# PSocC_Motor_Driver_Design_3.net
KiCad netlist of a schematic drawn in EAGLE
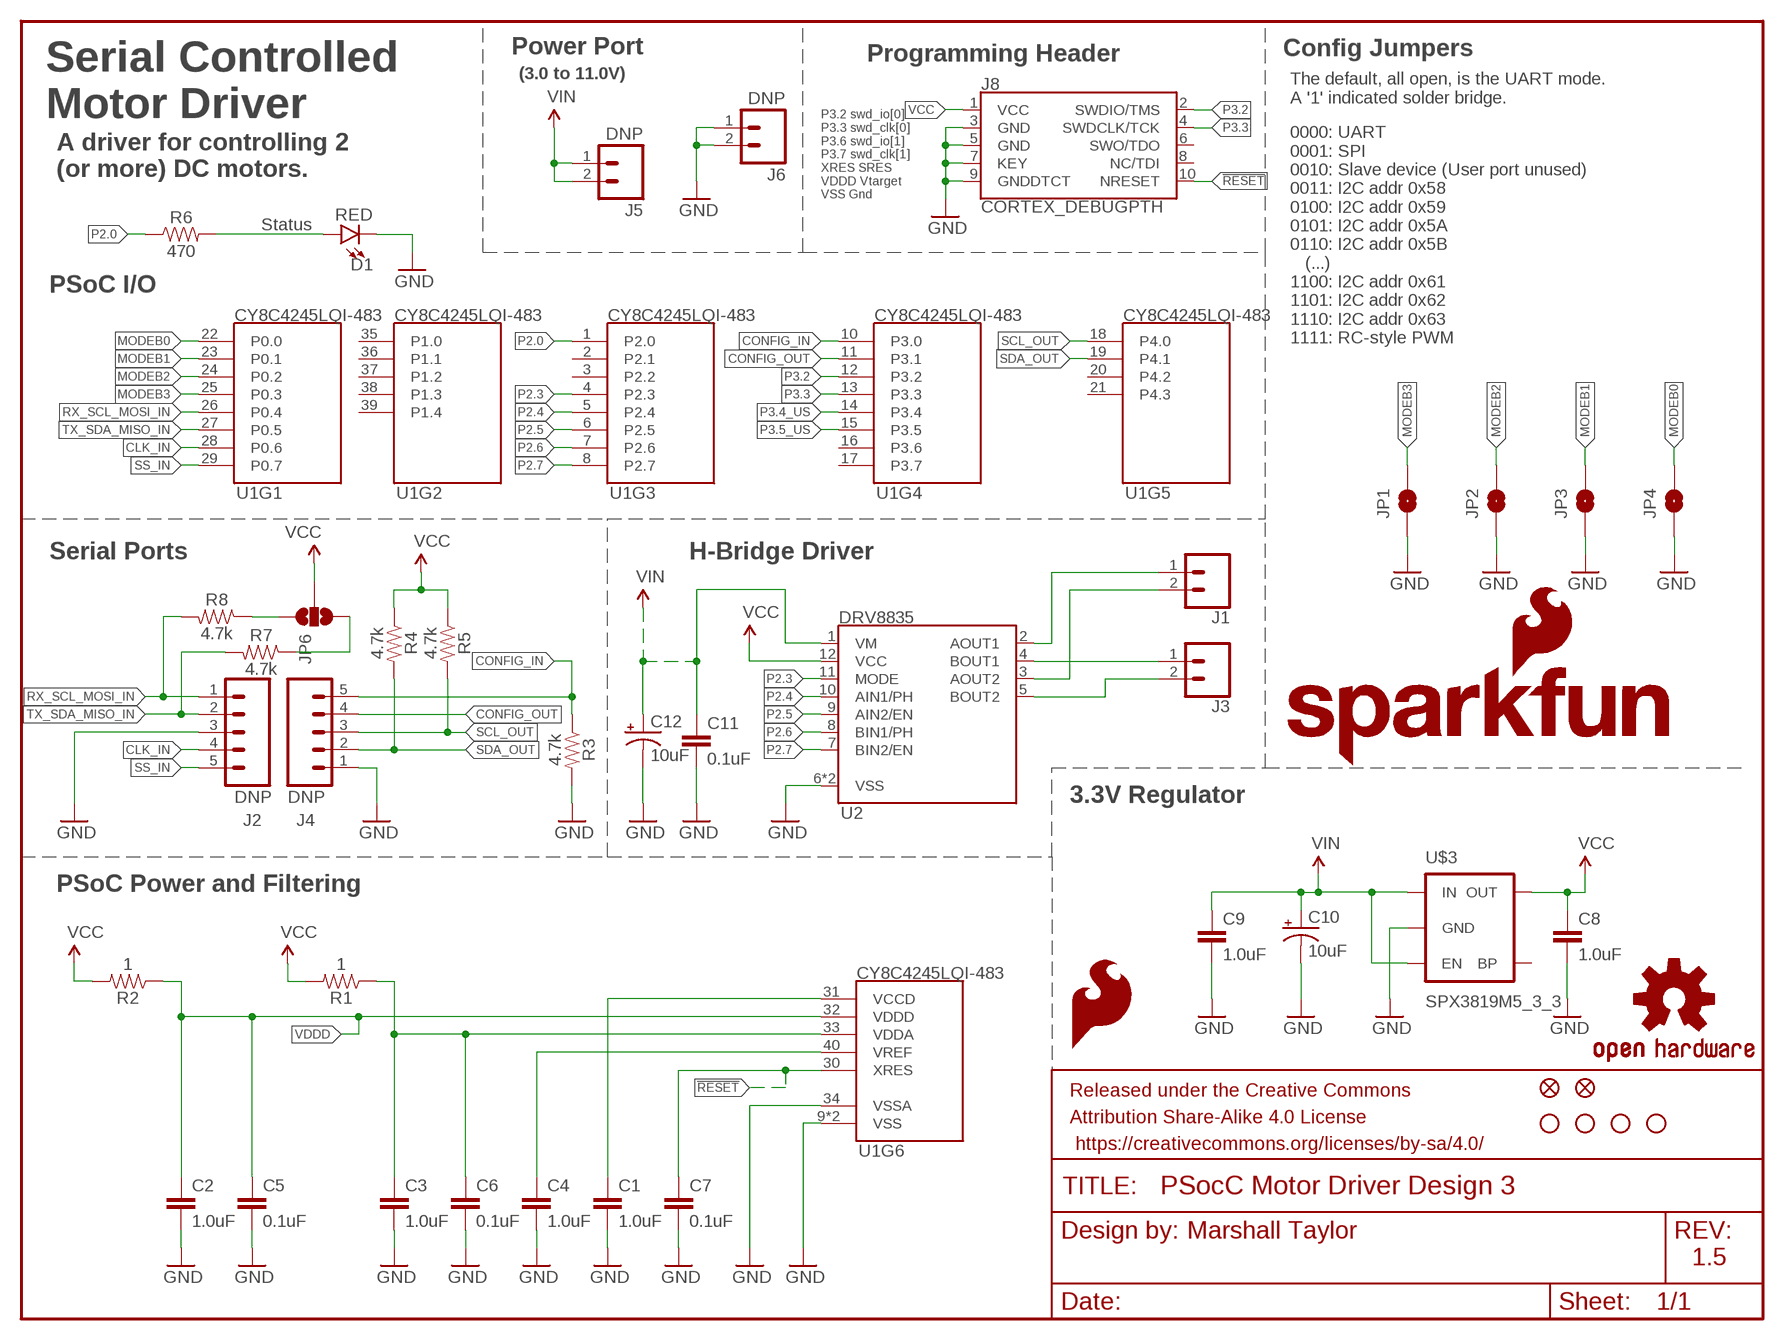
[diagram p0: schematic, sheet 1]

(export (version "E")
  (design (tool "Eeschema 10.0.6"))
  (components
    (comp (ref "C1")
      (value "1.0uF")
      (footprint "eagle-import:0402")
      (libsource (lib "eagle-import") (part "1.0UF-0402-16V-10%"))
    )
    (comp (ref "C2")
      (value "1.0uF")
      (footprint "eagle-import:0402")
      (libsource (lib "eagle-import") (part "1.0UF-0402-16V-10%"))
    )
    (comp (ref "C3")
      (value "1.0uF")
      (footprint "eagle-import:0402")
      (libsource (lib "eagle-import") (part "1.0UF-0402-16V-10%"))
    )
    (comp (ref "C4")
      (value "1.0uF")
      (footprint "eagle-import:0402")
      (libsource (lib "eagle-import") (part "1.0UF-0402-16V-10%"))
    )
    (comp (ref "C5")
      (value "0.1uF")
      (footprint "eagle-import:0402")
      (libsource (lib "eagle-import") (part "0.1UF-0402-16V-10%"))
    )
    (comp (ref "C6")
      (value "0.1uF")
      (footprint "eagle-import:0402")
      (libsource (lib "eagle-import") (part "0.1UF-0402-16V-10%"))
    )
    (comp (ref "C7")
      (value "0.1uF")
      (footprint "eagle-import:0402")
      (libsource (lib "eagle-import") (part "0.1UF-0402-16V-10%"))
    )
    (comp (ref "C8")
      (value "1.0uF")
      (footprint "eagle-import:0402")
      (libsource (lib "eagle-import") (part "1.0UF-0402-16V-10%"))
    )
    (comp (ref "C9")
      (value "1.0uF")
      (footprint "eagle-import:0402")
      (libsource (lib "eagle-import") (part "1.0UF-0402-16V-10%"))
    )
    (comp (ref "C10")
      (value "10uF")
      (footprint "eagle-import:EIA3216")
      (libsource (lib "eagle-import") (part "10UF-POLAR-EIA3216-16V-10%(TANT)"))
    )
    (comp (ref "C11")
      (value "0.1uF")
      (footprint "eagle-import:0402")
      (libsource (lib "eagle-import") (part "0.1UF-0402-16V-10%"))
    )
    (comp (ref "C12")
      (value "10uF")
      (footprint "eagle-import:EIA3216")
      (libsource (lib "eagle-import") (part "10UF-POLAR-EIA3216-16V-10%(TANT)"))
    )
    (comp (ref "D1")
      (value "RED")
      (footprint "eagle-import:LED-0603")
      (libsource (lib "eagle-import") (part "LED-RED0603"))
    )
    (comp (ref "FD1")
      (value "FIDUCIALUFIDUCIAL")
      (footprint "eagle-import:MICRO-FIDUCIAL")
      (libsource (lib "eagle-import") (part "FIDUCIALUFIDUCIAL"))
    )
    (comp (ref "FD2")
      (value "FIDUCIALUFIDUCIAL")
      (footprint "eagle-import:MICRO-FIDUCIAL")
      (libsource (lib "eagle-import") (part "FIDUCIALUFIDUCIAL"))
    )
    (comp (ref "FRAME1")
      (value "FRAME-LETTER")
      (footprint "eagle-import:CREATIVE_COMMONS")
      (libsource (lib "eagle-import") (part "FRAME-LETTER"))
    )
    (comp (ref "H1")
      (value "STAND-OFF")
      (footprint "eagle-import:STAND-OFF")
      (libsource (lib "eagle-import") (part "STAND-OFF"))
    )
    (comp (ref "H2")
      (value "STAND-OFF")
      (footprint "eagle-import:STAND-OFF")
      (libsource (lib "eagle-import") (part "STAND-OFF"))
    )
    (comp (ref "H3")
      (value "STAND-OFF")
      (footprint "eagle-import:STAND-OFF")
      (libsource (lib "eagle-import") (part "STAND-OFF"))
    )
    (comp (ref "H4")
      (value "STAND-OFF")
      (footprint "eagle-import:STAND-OFF")
      (libsource (lib "eagle-import") (part "STAND-OFF"))
    )
    (comp (ref "J1")
      (value "CONN_021X02_NO_SILK")
      (footprint "eagle-import:1X02_NO_SILK")
      (libsource (lib "eagle-import") (part "CONN_021X02_NO_SILK"))
    )
    (comp (ref "J2")
      (value "DNP")
      (footprint "eagle-import:1X05")
      (libsource (lib "eagle-import") (part "M05PTH"))
    )
    (comp (ref "J3")
      (value "CONN_021X02_NO_SILK")
      (footprint "eagle-import:1X02_NO_SILK")
      (libsource (lib "eagle-import") (part "CONN_021X02_NO_SILK"))
    )
    (comp (ref "J4")
      (value "DNP")
      (footprint "eagle-import:1X05")
      (libsource (lib "eagle-import") (part "M05PTH"))
    )
    (comp (ref "J5")
      (value "DNP")
      (footprint "eagle-import:1X02@1")
      (libsource (lib "eagle-import") (part "M02PTH"))
    )
    (comp (ref "J6")
      (value "DNP")
      (footprint "eagle-import:1X02@1")
      (libsource (lib "eagle-import") (part "M02PTH"))
    )
    (comp (ref "J8")
      (value "CORTEX_DEBUGPTH")
      (footprint "eagle-import:2X5-PTH-1.27MM")
      (libsource (lib "eagle-import") (part "CORTEX_DEBUGPTH"))
    )
    (comp (ref "JP1")
      (value "JUMPER-PAD-2")
      (footprint "eagle-import:PAD-JUMPER-2-NO_YES_SILK")
      (libsource (lib "eagle-import") (part "JUMPER-PAD-2-NOYES_SILK"))
    )
    (comp (ref "JP2")
      (value "JUMPER-PAD-2")
      (footprint "eagle-import:PAD-JUMPER-2-NO_YES_SILK")
      (libsource (lib "eagle-import") (part "JUMPER-PAD-2-NOYES_SILK"))
    )
    (comp (ref "JP3")
      (value "JUMPER-PAD-2")
      (footprint "eagle-import:PAD-JUMPER-2-NO_YES_SILK")
      (libsource (lib "eagle-import") (part "JUMPER-PAD-2-NOYES_SILK"))
    )
    (comp (ref "JP4")
      (value "JUMPER-PAD-2")
      (footprint "eagle-import:PAD-JUMPER-2-NO_YES_SILK")
      (libsource (lib "eagle-import") (part "JUMPER-PAD-2-NOYES_SILK"))
    )
    (comp (ref "JP6")
      (value "JUMPER-PAD-3-NOYES_SILK")
      (footprint "eagle-import:PAD-JUMPER-3-NO_YES_SILK")
      (libsource (lib "eagle-import") (part "JUMPER-PAD-3-NOYES_SILK"))
    )
    (comp (ref "LOGO1")
      (value "SFE_LOGO_FLAME.1_INCH")
      (footprint "eagle-import:SFE_LOGO_FLAME_.1")
      (libsource (lib "eagle-import") (part "SFE_LOGO_FLAME.1_INCH"))
    )
    (comp (ref "LOGO2")
      (value "OSHW-LOGOMINI")
      (footprint "eagle-import:OSHW-LOGO-MINI")
      (libsource (lib "eagle-import") (part "OSHW-LOGOMINI"))
    )
    (comp (ref "LOGO3")
      (value "SFE_LOGO_NAME_FLAME.1_INCH")
      (footprint "eagle-import:SFE_LOGO_NAME_FLAME_.1")
      (libsource (lib "eagle-import") (part "SFE_LOGO_NAME_FLAME.1_INCH"))
    )
    (comp (ref "R1")
      (value "1")
      (footprint "eagle-import:0603")
      (libsource (lib "eagle-import") (part "1OHM-0603-1/10W-1%"))
    )
    (comp (ref "R2")
      (value "1")
      (footprint "eagle-import:0603")
      (libsource (lib "eagle-import") (part "1OHM-0603-1/10W-1%"))
    )
    (comp (ref "R3")
      (value "4.7k")
      (footprint "eagle-import:0603")
      (libsource (lib "eagle-import") (part "4.7KOHM-0603-1/10W-1%"))
    )
    (comp (ref "R4")
      (value "4.7k")
      (footprint "eagle-import:0603")
      (libsource (lib "eagle-import") (part "4.7KOHM-0603-1/10W-1%"))
    )
    (comp (ref "R5")
      (value "4.7k")
      (footprint "eagle-import:0603")
      (libsource (lib "eagle-import") (part "4.7KOHM-0603-1/10W-1%"))
    )
    (comp (ref "R6")
      (value "470")
      (footprint "eagle-import:0603")
      (libsource (lib "eagle-import") (part "470OHM-0603-1/10W-1%"))
    )
    (comp (ref "R7")
      (value "4.7k")
      (footprint "eagle-import:0603")
      (libsource (lib "eagle-import") (part "4.7KOHM-0603-1/10W-1%"))
    )
    (comp (ref "R8")
      (value "4.7k")
      (footprint "eagle-import:0603")
      (libsource (lib "eagle-import") (part "4.7KOHM-0603-1/10W-1%"))
    )
    (comp (ref "U$3")
      (value "SPX3819M5_3_3")
      (footprint "eagle-import:SOT-23-5-VREG")
      (libsource (lib "eagle-import") (part "SPX3819"))
    )
    (comp (ref "U1")
      (value "CY8C4245LQI-483")
      (footprint "eagle-import:QFN-40")
      (libsource (lib "eagle-import") (part "CY8C4245LQI"))
    )
    (comp (ref "U2")
      (value "DRV8835")
      (footprint "eagle-import:WSON-12")
      (fields (field (name "PROD_ID") "IC-13342"))
      (libsource (lib "eagle-import") (part "DRV883X"))
    )
  )
  (nets
    (net (code "1") (name "/~{RESET}") (class "Default")
      (node (ref "C7") (pin "1") (pinfunction "1_1") (pintype "passive"))
      (node (ref "J8") (pin "10") (pinfunction "NRESET_10") (pintype "bidirectional"))
      (node (ref "U1") (pin "30") (pinfunction "XRES_30") (pintype "bidirectional"))
    )
    (net (code "2") (name "CLK_IN") (class "Default")
      (node (ref "J2") (pin "4") (pinfunction "4_4") (pintype "passive"))
      (node (ref "U1") (pin "28") (pinfunction "P0.6_28") (pintype "bidirectional"))
    )
    (net (code "3") (name "CONFIG_IN") (class "Default")
      (node (ref "J4") (pin "5") (pinfunction "5_5") (pintype "passive"))
      (node (ref "R3") (pin "1") (pinfunction "1_1") (pintype "passive"))
      (node (ref "U1") (pin "10") (pinfunction "P3.0_10") (pintype "bidirectional"))
    )
    (net (code "4") (name "CONFIG_OUT") (class "Default")
      (node (ref "J4") (pin "4") (pinfunction "4_4") (pintype "passive"))
      (node (ref "U1") (pin "11") (pinfunction "P3.1_11") (pintype "bidirectional"))
    )
    (net (code "5") (name "GND") (class "Default")
      (node (ref "C1") (pin "2") (pinfunction "2_2") (pintype "passive"))
      (node (ref "C10") (pin "-") (pinfunction "-_-") (pintype "passive"))
      (node (ref "C11") (pin "2") (pinfunction "2_2") (pintype "passive"))
      (node (ref "C12") (pin "-") (pinfunction "-_-") (pintype "passive"))
      (node (ref "C2") (pin "2") (pinfunction "2_2") (pintype "passive"))
      (node (ref "C3") (pin "2") (pinfunction "2_2") (pintype "passive"))
      (node (ref "C4") (pin "2") (pinfunction "2_2") (pintype "passive"))
      (node (ref "C5") (pin "2") (pinfunction "2_2") (pintype "passive"))
      (node (ref "C6") (pin "2") (pinfunction "2_2") (pintype "passive"))
      (node (ref "C7") (pin "2") (pinfunction "2_2") (pintype "passive"))
      (node (ref "C8") (pin "2") (pinfunction "2_2") (pintype "passive"))
      (node (ref "C9") (pin "2") (pinfunction "2_2") (pintype "passive"))
      (node (ref "D1") (pin "C") (pinfunction "C_C") (pintype "passive"))
      (node (ref "J2") (pin "3") (pinfunction "3_3") (pintype "passive"))
      (node (ref "J4") (pin "1") (pinfunction "1_1") (pintype "passive"))
      (node (ref "J6") (pin "1") (pinfunction "1_1") (pintype "passive"))
      (node (ref "J6") (pin "2") (pinfunction "2_2") (pintype "passive"))
      (node (ref "J8") (pin "3") (pinfunction "GND_3") (pintype "bidirectional"))
      (node (ref "J8") (pin "5") (pinfunction "GND_5") (pintype "bidirectional"))
      (node (ref "J8") (pin "7") (pinfunction "KEY_7") (pintype "bidirectional"))
      (node (ref "J8") (pin "9") (pinfunction "GNDDTCT_9") (pintype "bidirectional"))
      (node (ref "JP1") (pin "1") (pinfunction "1_1") (pintype "passive"))
      (node (ref "JP2") (pin "1") (pinfunction "1_1") (pintype "passive"))
      (node (ref "JP3") (pin "1") (pinfunction "1_1") (pintype "passive"))
      (node (ref "JP4") (pin "1") (pinfunction "1_1") (pintype "passive"))
      (node (ref "R3") (pin "2") (pinfunction "2_2") (pintype "passive"))
      (node (ref "U$3") (pin "2") (pinfunction "GND_2") (pintype "input"))
      (node (ref "U1") (pin "34") (pinfunction "VSSA_34") (pintype "bidirectional"))
      (node (ref "U1") (pin "9") (pinfunction "VSS_9") (pintype "bidirectional"))
      (node (ref "U1") (pin "EP") (pinfunction "VSS_EP") (pintype "bidirectional"))
      (node (ref "U2") (pin "6") (pinfunction "VSS_6") (pintype "bidirectional"))
      (node (ref "U2") (pin "PAD") (pinfunction "VSS_PAD") (pintype "bidirectional"))
    )
    (net (code "6") (name "MODEB0") (class "Default")
      (node (ref "JP4") (pin "2") (pinfunction "2_2") (pintype "passive"))
      (node (ref "U1") (pin "22") (pinfunction "P0.0_22") (pintype "bidirectional"))
    )
    (net (code "7") (name "MODEB1") (class "Default")
      (node (ref "JP3") (pin "2") (pinfunction "2_2") (pintype "passive"))
      (node (ref "U1") (pin "23") (pinfunction "P0.1_23") (pintype "bidirectional"))
    )
    (net (code "8") (name "MODEB2") (class "Default")
      (node (ref "JP2") (pin "2") (pinfunction "2_2") (pintype "passive"))
      (node (ref "U1") (pin "24") (pinfunction "P0.2_24") (pintype "bidirectional"))
    )
    (net (code "9") (name "MODEB3") (class "Default")
      (node (ref "JP1") (pin "2") (pinfunction "2_2") (pintype "passive"))
      (node (ref "U1") (pin "25") (pinfunction "P0.3_25") (pintype "bidirectional"))
    )
    (net (code "10") (name "Net-(D1-PadA)") (class "Default")
      (node (ref "D1") (pin "A") (pinfunction "A_A") (pintype "passive"))
      (node (ref "R6") (pin "2") (pinfunction "2_2") (pintype "passive"))
    )
    (net (code "11") (name "Net-(JP6-Pad1)") (class "Default")
      (node (ref "JP6") (pin "1") (pinfunction "1_1") (pintype "passive"))
      (node (ref "R8") (pin "1") (pinfunction "1_1") (pintype "passive"))
    )
    (net (code "12") (name "Net-(JP6-Pad3)") (class "Default")
      (node (ref "JP6") (pin "3") (pinfunction "3_3") (pintype "passive"))
      (node (ref "R7") (pin "1") (pinfunction "1_1") (pintype "passive"))
    )
    (net (code "13") (name "Net-(U1F-VCCD)") (class "Default")
      (node (ref "C1") (pin "1") (pinfunction "1_1") (pintype "passive"))
      (node (ref "U1") (pin "31") (pinfunction "VCCD_31") (pintype "bidirectional"))
    )
    (net (code "14") (name "Net-(U1F-VDDA)") (class "Default")
      (node (ref "C3") (pin "1") (pinfunction "1_1") (pintype "passive"))
      (node (ref "C6") (pin "1") (pinfunction "1_1") (pintype "passive"))
      (node (ref "R1") (pin "1") (pinfunction "1_1") (pintype "passive"))
      (node (ref "U1") (pin "33") (pinfunction "VDDA_33") (pintype "bidirectional"))
    )
    (net (code "15") (name "Net-(U1F-VREF)") (class "Default")
      (node (ref "C4") (pin "1") (pinfunction "1_1") (pintype "passive"))
      (node (ref "U1") (pin "40") (pinfunction "VREF_40") (pintype "bidirectional"))
    )
    (net (code "16") (name "Net-(U2-AOUT1)") (class "Default")
      (node (ref "J1") (pin "1") (pinfunction "1_1") (pintype "passive"))
      (node (ref "U2") (pin "2") (pinfunction "AOUT1_2") (pintype "bidirectional"))
    )
    (net (code "17") (name "Net-(U2-AOUT2)") (class "Default")
      (node (ref "J1") (pin "2") (pinfunction "2_2") (pintype "passive"))
      (node (ref "U2") (pin "3") (pinfunction "AOUT2_3") (pintype "bidirectional"))
    )
    (net (code "18") (name "Net-(U2-BOUT1)") (class "Default")
      (node (ref "J3") (pin "1") (pinfunction "1_1") (pintype "passive"))
      (node (ref "U2") (pin "4") (pinfunction "BOUT1_4") (pintype "bidirectional"))
    )
    (net (code "19") (name "Net-(U2-BOUT2)") (class "Default")
      (node (ref "J3") (pin "2") (pinfunction "2_2") (pintype "passive"))
      (node (ref "U2") (pin "5") (pinfunction "BOUT2_5") (pintype "bidirectional"))
    )
    (net (code "20") (name "P2.0") (class "Default")
      (node (ref "R6") (pin "1") (pinfunction "1_1") (pintype "passive"))
      (node (ref "U1") (pin "1") (pinfunction "P2.0_1") (pintype "bidirectional"))
    )
    (net (code "21") (name "P2.3") (class "Default")
      (node (ref "U1") (pin "4") (pinfunction "P2.3_4") (pintype "bidirectional"))
      (node (ref "U2") (pin "11") (pinfunction "MODE_11") (pintype "bidirectional"))
    )
    (net (code "22") (name "P2.4") (class "Default")
      (node (ref "U1") (pin "5") (pinfunction "P2.4_5") (pintype "bidirectional"))
      (node (ref "U2") (pin "10") (pinfunction "AIN1/PH_10") (pintype "bidirectional"))
    )
    (net (code "23") (name "P2.5") (class "Default")
      (node (ref "U1") (pin "6") (pinfunction "P2.5_6") (pintype "bidirectional"))
      (node (ref "U2") (pin "9") (pinfunction "AIN2/EN_9") (pintype "bidirectional"))
    )
    (net (code "24") (name "P2.6") (class "Default")
      (node (ref "U1") (pin "7") (pinfunction "P2.6_7") (pintype "bidirectional"))
      (node (ref "U2") (pin "8") (pinfunction "BIN1/PH_8") (pintype "bidirectional"))
    )
    (net (code "25") (name "P2.7") (class "Default")
      (node (ref "U1") (pin "8") (pinfunction "P2.7_8") (pintype "bidirectional"))
      (node (ref "U2") (pin "7") (pinfunction "BIN2/EN_7") (pintype "bidirectional"))
    )
    (net (code "26") (name "P3.2") (class "Default")
      (node (ref "J8") (pin "2") (pinfunction "SWDIO/TMS_2") (pintype "bidirectional"))
      (node (ref "U1") (pin "12") (pinfunction "P3.2_12") (pintype "bidirectional"))
    )
    (net (code "27") (name "P3.3") (class "Default")
      (node (ref "J8") (pin "4") (pinfunction "SWDCLK/TCK_4") (pintype "bidirectional"))
      (node (ref "U1") (pin "13") (pinfunction "P3.3_13") (pintype "bidirectional"))
    )
    (net (code "28") (name "P3.4_US") (class "Default")
      (node (ref "U1") (pin "14") (pinfunction "P3.4_14") (pintype "bidirectional"))
    )
    (net (code "29") (name "P3.5_US") (class "Default")
      (node (ref "U1") (pin "15") (pinfunction "P3.5_15") (pintype "bidirectional"))
    )
    (net (code "30") (name "RX_SCL_MOSI_IN") (class "Default")
      (node (ref "J2") (pin "1") (pinfunction "1_1") (pintype "passive"))
      (node (ref "R8") (pin "2") (pinfunction "2_2") (pintype "passive"))
      (node (ref "U1") (pin "26") (pinfunction "P0.4_26") (pintype "bidirectional"))
    )
    (net (code "31") (name "SCL_OUT") (class "Default")
      (node (ref "J4") (pin "3") (pinfunction "3_3") (pintype "passive"))
      (node (ref "R5") (pin "2") (pinfunction "2_2") (pintype "passive"))
      (node (ref "U1") (pin "18") (pinfunction "P4.0_18") (pintype "bidirectional"))
    )
    (net (code "32") (name "SDA_OUT") (class "Default")
      (node (ref "J4") (pin "2") (pinfunction "2_2") (pintype "passive"))
      (node (ref "R4") (pin "2") (pinfunction "2_2") (pintype "passive"))
      (node (ref "U1") (pin "19") (pinfunction "P4.1_19") (pintype "bidirectional"))
    )
    (net (code "33") (name "SS_IN") (class "Default")
      (node (ref "J2") (pin "5") (pinfunction "5_5") (pintype "passive"))
      (node (ref "U1") (pin "29") (pinfunction "P0.7_29") (pintype "bidirectional"))
    )
    (net (code "34") (name "TX_SDA_MISO_IN") (class "Default")
      (node (ref "J2") (pin "2") (pinfunction "2_2") (pintype "passive"))
      (node (ref "R7") (pin "2") (pinfunction "2_2") (pintype "passive"))
      (node (ref "U1") (pin "27") (pinfunction "P0.5_27") (pintype "bidirectional"))
    )
    (net (code "35") (name "VCC") (class "Default")
      (node (ref "C8") (pin "1") (pinfunction "1_1") (pintype "passive"))
      (node (ref "J8") (pin "1") (pinfunction "VCC_1") (pintype "bidirectional"))
      (node (ref "JP6") (pin "2") (pinfunction "2_2") (pintype "passive"))
      (node (ref "R1") (pin "2") (pinfunction "2_2") (pintype "passive"))
      (node (ref "R2") (pin "2") (pinfunction "2_2") (pintype "passive"))
      (node (ref "R4") (pin "1") (pinfunction "1_1") (pintype "passive"))
      (node (ref "R5") (pin "1") (pinfunction "1_1") (pintype "passive"))
      (node (ref "U$3") (pin "5") (pinfunction "OUT_5") (pintype "passive"))
      (node (ref "U2") (pin "12") (pinfunction "VCC_12") (pintype "bidirectional"))
    )
    (net (code "36") (name "VDDD") (class "Default")
      (node (ref "C2") (pin "1") (pinfunction "1_1") (pintype "passive"))
      (node (ref "C5") (pin "1") (pinfunction "1_1") (pintype "passive"))
      (node (ref "R2") (pin "1") (pinfunction "1_1") (pintype "passive"))
      (node (ref "U1") (pin "32") (pinfunction "VDDD_32") (pintype "bidirectional"))
    )
    (net (code "37") (name "VIN") (class "Default")
      (node (ref "C10") (pin "+") (pinfunction "+_+") (pintype "passive"))
      (node (ref "C11") (pin "1") (pinfunction "1_1") (pintype "passive"))
      (node (ref "C12") (pin "+") (pinfunction "+_+") (pintype "passive"))
      (node (ref "C9") (pin "1") (pinfunction "1_1") (pintype "passive"))
      (node (ref "J5") (pin "1") (pinfunction "1_1") (pintype "passive"))
      (node (ref "J5") (pin "2") (pinfunction "2_2") (pintype "passive"))
      (node (ref "U$3") (pin "1") (pinfunction "IN_1") (pintype "input"))
      (node (ref "U$3") (pin "3") (pinfunction "EN_3") (pintype "input"))
      (node (ref "U2") (pin "1") (pinfunction "VM_1") (pintype "bidirectional"))
    )
    (net (code "38") (name "unconnected-(J8-NC{slash}TDI-Pad8)") (class "Default")
      (node (ref "J8") (pin "8") (pinfunction "NC/TDI_8") (pintype "bidirectional"))
    )
    (net (code "39") (name "unconnected-(J8-SWO{slash}TDO-Pad6)") (class "Default")
      (node (ref "J8") (pin "6") (pinfunction "SWO/TDO_6") (pintype "bidirectional"))
    )
    (net (code "40") (name "unconnected-(U$3-BP-Pad4)") (class "Default")
      (node (ref "U$3") (pin "4") (pinfunction "BP_4") (pintype "input"))
    )
    (net (code "41") (name "unconnected-(U1B-P1.0-Pad35)") (class "Default")
      (node (ref "U1") (pin "35") (pinfunction "P1.0_35") (pintype "bidirectional"))
    )
    (net (code "42") (name "unconnected-(U1B-P1.1-Pad36)") (class "Default")
      (node (ref "U1") (pin "36") (pinfunction "P1.1_36") (pintype "bidirectional"))
    )
    (net (code "43") (name "unconnected-(U1B-P1.2-Pad37)") (class "Default")
      (node (ref "U1") (pin "37") (pinfunction "P1.2_37") (pintype "bidirectional"))
    )
    (net (code "44") (name "unconnected-(U1B-P1.3-Pad38)") (class "Default")
      (node (ref "U1") (pin "38") (pinfunction "P1.3_38") (pintype "bidirectional"))
    )
    (net (code "45") (name "unconnected-(U1B-P1.4-Pad39)") (class "Default")
      (node (ref "U1") (pin "39") (pinfunction "P1.4_39") (pintype "bidirectional"))
    )
    (net (code "46") (name "unconnected-(U1C-P2.1-Pad2)") (class "Default")
      (node (ref "U1") (pin "2") (pinfunction "P2.1_2") (pintype "bidirectional"))
    )
    (net (code "47") (name "unconnected-(U1C-P2.2-Pad3)") (class "Default")
      (node (ref "U1") (pin "3") (pinfunction "P2.2_3") (pintype "bidirectional"))
    )
    (net (code "48") (name "unconnected-(U1D-P3.6-Pad16)") (class "Default")
      (node (ref "U1") (pin "16") (pinfunction "P3.6_16") (pintype "bidirectional"))
    )
    (net (code "49") (name "unconnected-(U1D-P3.7-Pad17)") (class "Default")
      (node (ref "U1") (pin "17") (pinfunction "P3.7_17") (pintype "bidirectional"))
    )
    (net (code "50") (name "unconnected-(U1E-P4.2-Pad20)") (class "Default")
      (node (ref "U1") (pin "20") (pinfunction "P4.2_20") (pintype "bidirectional"))
    )
    (net (code "51") (name "unconnected-(U1E-P4.3-Pad21)") (class "Default")
      (node (ref "U1") (pin "21") (pinfunction "P4.3_21") (pintype "bidirectional"))
    )
  )
)
